# servodriver.net
KiCad netlist of a schematic drawn in EAGLE
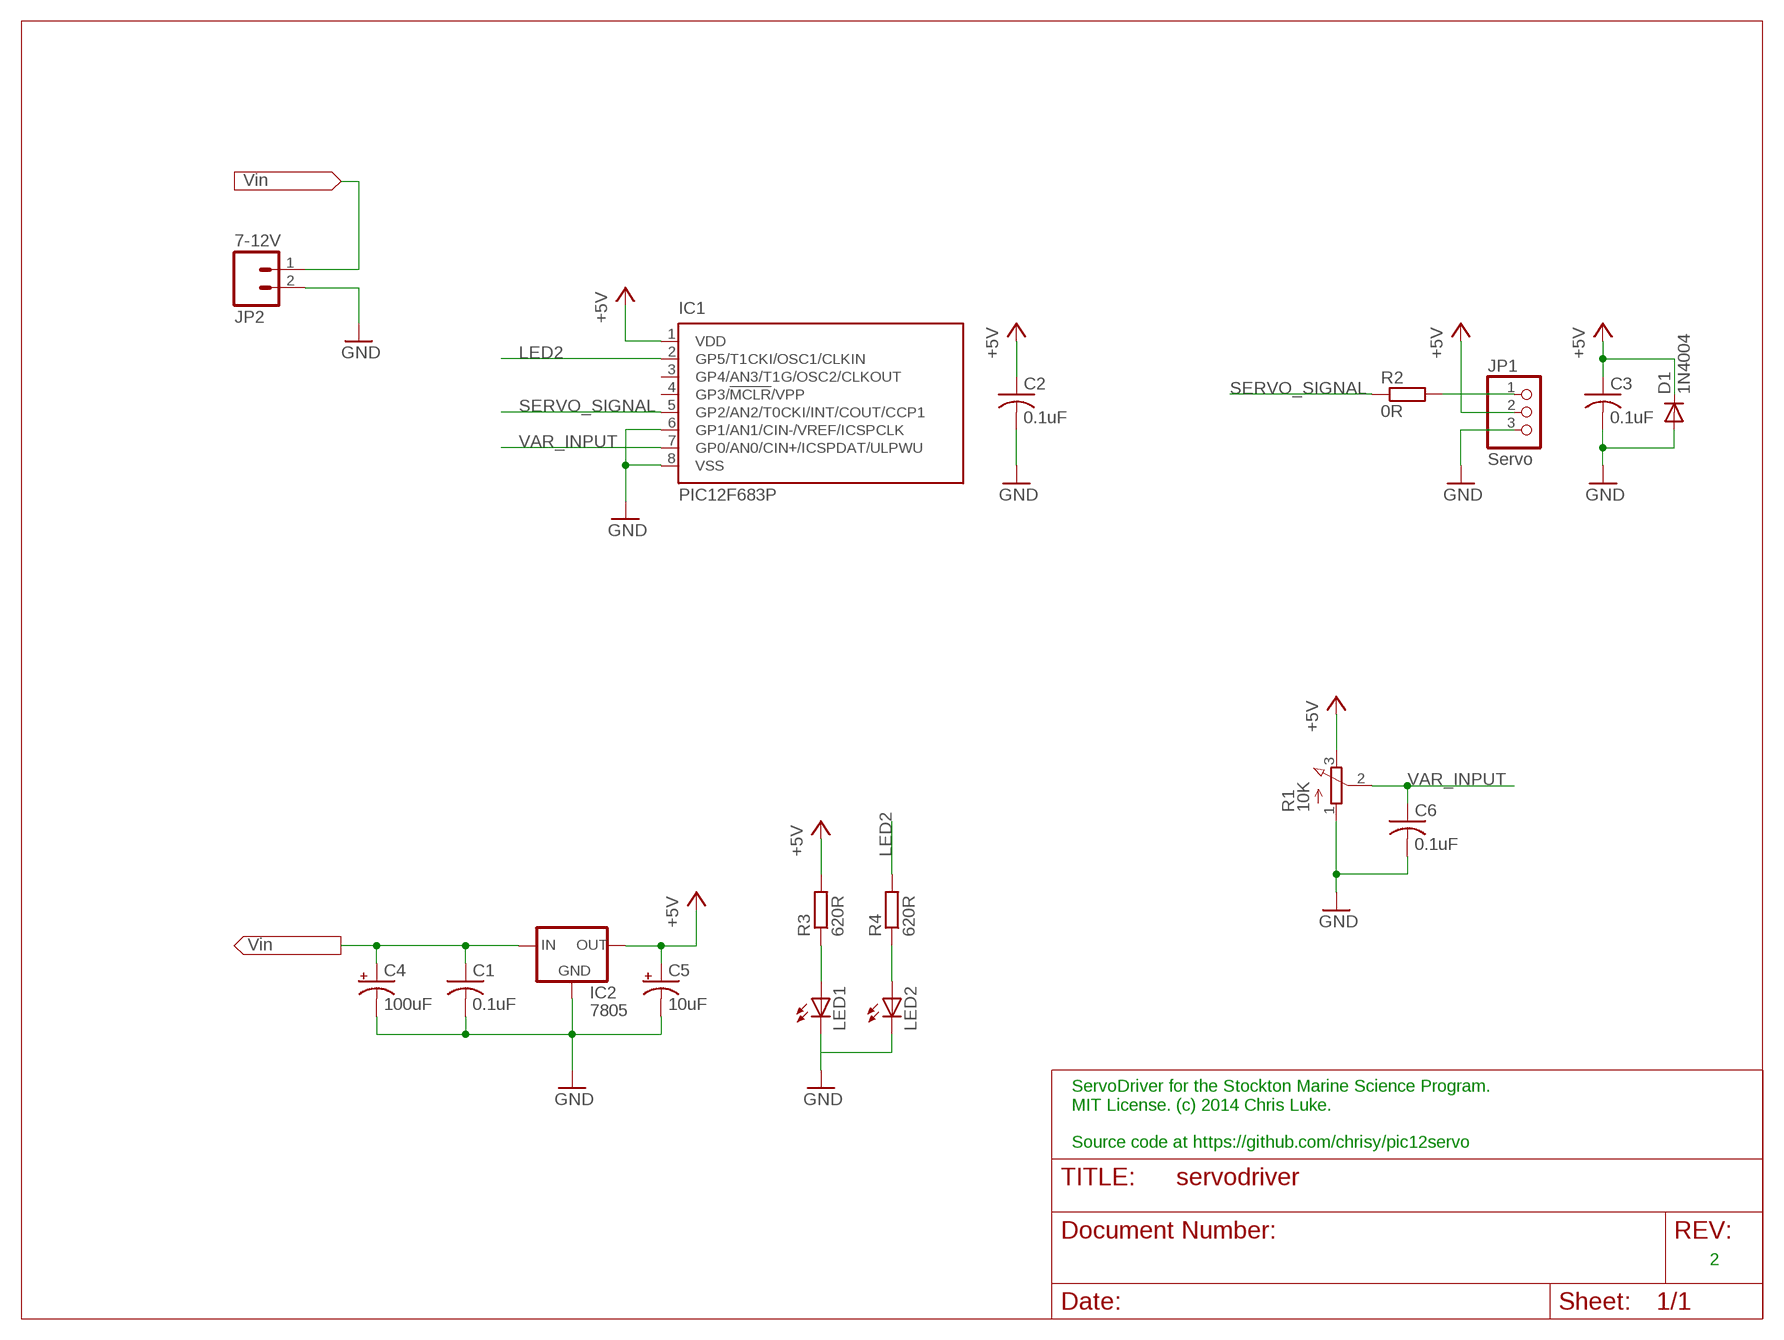
[diagram p0: schematic, sheet 1]

(export (version "E")
  (design (tool "Eeschema 10.0.6"))
  (components
    (comp (ref "C1")
      (value "0.1uF")
      (footprint "eagle-import:C025-025X050")
      (libsource (lib "eagle-import") (part "C-US025-025X050"))
    )
    (comp (ref "C2")
      (value "0.1uF")
      (footprint "eagle-import:C025-025X050")
      (libsource (lib "eagle-import") (part "C-US025-025X050"))
    )
    (comp (ref "C3")
      (value "0.1uF")
      (footprint "eagle-import:C025-025X050")
      (libsource (lib "eagle-import") (part "C-US025-025X050"))
    )
    (comp (ref "C4")
      (value "100uF")
      (footprint "eagle-import:E2,5-6")
      (libsource (lib "eagle-import") (part "CPOL-USE2.5-6"))
    )
    (comp (ref "C5")
      (value "10uF")
      (footprint "eagle-import:E2,5-6")
      (libsource (lib "eagle-import") (part "CPOL-USE2.5-6"))
    )
    (comp (ref "C6")
      (value "0.1uF")
      (footprint "eagle-import:C025-025X050")
      (libsource (lib "eagle-import") (part "C-US025-025X050"))
    )
    (comp (ref "D1")
      (value "1N4004")
      (footprint "eagle-import:DO41-10")
      (libsource (lib "eagle-import") (part "1N4004"))
    )
    (comp (ref "IC1")
      (value "PIC12F683P")
      (footprint "eagle-import:DIL8")
      (fields (field (name "MF") "MICROCHIP") (field (name "MPN") "PIC12F683-I/P"))
      (libsource (lib "eagle-import") (part "PIC12F683P"))
    )
    (comp (ref "IC2")
      (value "7805")
      (footprint "eagle-import:78XXL")
      (libsource (lib "eagle-import") (part "78XXL"))
    )
    (comp (ref "JP1")
      (value "Servo")
      (footprint "eagle-import:1X03")
      (libsource (lib "eagle-import") (part "PINHD-1X3"))
    )
    (comp (ref "JP2")
      (value "7-12V")
      (footprint "eagle-import:SCREWTERMINAL-3.5MM-2")
      (libsource (lib "eagle-import") (part "M023.5MM"))
    )
    (comp (ref "LED1")
      (value "LED3MM")
      (footprint "eagle-import:LED3MM")
      (libsource (lib "eagle-import") (part "LED3MM"))
    )
    (comp (ref "LED2")
      (value "LED3MM")
      (footprint "eagle-import:LED3MM")
      (libsource (lib "eagle-import") (part "LED3MM"))
    )
    (comp (ref "R1")
      (value "10K")
      (footprint "eagle-import:3RP_1610N")
      (libsource (lib "eagle-import") (part "3RP/1610N"))
    )
    (comp (ref "R2")
      (value "0R")
      (footprint "eagle-import:0207_10")
      (libsource (lib "eagle-import") (part "R-EU_0207/10"))
    )
    (comp (ref "R3")
      (value "620R")
      (footprint "eagle-import:0207_10")
      (libsource (lib "eagle-import") (part "R-EU_0207/10"))
    )
    (comp (ref "R4")
      (value "620R")
      (footprint "eagle-import:0207_10")
      (libsource (lib "eagle-import") (part "R-EU_0207/10"))
    )
  )
  (nets
    (net (code "1") (name "+5V") (class "Default")
      (node (ref "C2") (pin "1") (pinfunction "1_1") (pintype "passive"))
      (node (ref "C3") (pin "1") (pinfunction "1_1") (pintype "passive"))
      (node (ref "C5") (pin "+") (pinfunction "+_+") (pintype "passive"))
      (node (ref "D1") (pin "C") (pinfunction "C_C") (pintype "passive"))
      (node (ref "IC1") (pin "1") (pinfunction "VDD_1") (pintype "power_in"))
      (node (ref "IC2") (pin "OUT") (pinfunction "OUT_OUT") (pintype "passive"))
      (node (ref "JP1") (pin "2") (pinfunction "2_2") (pintype "passive"))
      (node (ref "R1") (pin "3") (pinfunction "E_3") (pintype "passive"))
      (node (ref "R3") (pin "2") (pinfunction "2_2") (pintype "passive"))
    )
    (net (code "2") (name "/LED2") (class "Default")
      (node (ref "IC1") (pin "2") (pinfunction "GP5/T1CKI/OSC1/CLKIN_2") (pintype "bidirectional"))
      (node (ref "R4") (pin "2") (pinfunction "2_2") (pintype "passive"))
    )
    (net (code "3") (name "/SERVO_SIGNAL") (class "Default")
      (node (ref "IC1") (pin "5") (pinfunction "GP2/AN2/T0CKI/INT/COUT/CCP1_5") (pintype "bidirectional"))
      (node (ref "R2") (pin "1") (pinfunction "1_1") (pintype "passive"))
    )
    (net (code "4") (name "/VAR_INPUT") (class "Default")
      (node (ref "C6") (pin "1") (pinfunction "1_1") (pintype "passive"))
      (node (ref "IC1") (pin "7") (pinfunction "GP0/AN0/CIN+/ICSPDAT/ULPWU_7") (pintype "bidirectional"))
      (node (ref "R1") (pin "2") (pinfunction "S_2") (pintype "passive"))
    )
    (net (code "5") (name "/VIN") (class "Default")
      (node (ref "C1") (pin "1") (pinfunction "1_1") (pintype "passive"))
      (node (ref "C4") (pin "+") (pinfunction "+_+") (pintype "passive"))
      (node (ref "IC2") (pin "IN") (pinfunction "IN_IN") (pintype "input"))
      (node (ref "JP2") (pin "1") (pinfunction "1_1") (pintype "passive"))
    )
    (net (code "6") (name "GND") (class "Default")
      (node (ref "C1") (pin "2") (pinfunction "2_2") (pintype "passive"))
      (node (ref "C2") (pin "2") (pinfunction "2_2") (pintype "passive"))
      (node (ref "C3") (pin "2") (pinfunction "2_2") (pintype "passive"))
      (node (ref "C4") (pin "-") (pinfunction "-_-") (pintype "passive"))
      (node (ref "C5") (pin "-") (pinfunction "-_-") (pintype "passive"))
      (node (ref "C6") (pin "2") (pinfunction "2_2") (pintype "passive"))
      (node (ref "D1") (pin "A") (pinfunction "A_A") (pintype "passive"))
      (node (ref "IC1") (pin "6") (pinfunction "GP1/AN1/CIN-/VREF/ICSPCLK_6") (pintype "bidirectional"))
      (node (ref "IC1") (pin "8") (pinfunction "VSS_8") (pintype "power_in"))
      (node (ref "IC2") (pin "GND") (pinfunction "GND_GND") (pintype "input"))
      (node (ref "JP1") (pin "3") (pinfunction "3_3") (pintype "passive"))
      (node (ref "JP2") (pin "2") (pinfunction "2_2") (pintype "passive"))
      (node (ref "LED1") (pin "K") (pinfunction "C_K") (pintype "passive"))
      (node (ref "LED2") (pin "K") (pinfunction "C_K") (pintype "passive"))
      (node (ref "R1") (pin "1") (pinfunction "A_1") (pintype "passive"))
    )
    (net (code "7") (name "Net-(JP1-Pad1)") (class "Default")
      (node (ref "JP1") (pin "1") (pinfunction "1_1") (pintype "passive"))
      (node (ref "R2") (pin "2") (pinfunction "2_2") (pintype "passive"))
    )
    (net (code "8") (name "Net-(LED1-PadA)") (class "Default")
      (node (ref "LED1") (pin "A") (pinfunction "A_A") (pintype "passive"))
      (node (ref "R3") (pin "1") (pinfunction "1_1") (pintype "passive"))
    )
    (net (code "9") (name "Net-(LED2-PadA)") (class "Default")
      (node (ref "LED2") (pin "A") (pinfunction "A_A") (pintype "passive"))
      (node (ref "R4") (pin "1") (pinfunction "1_1") (pintype "passive"))
    )
    (net (code "10") (name "unconnected-(IC1-GP3{slash}~{MCLR}{slash}VPP-Pad4)") (class "Default")
      (node (ref "IC1") (pin "4") (pinfunction "GP3/~{MCLR}/VPP_4") (pintype "bidirectional"))
    )
    (net (code "11") (name "unconnected-(IC1-GP4{slash}AN3{slash}T1G{slash}OSC2{slash}CLKOUT-Pad3)") (class "Default")
      (node (ref "IC1") (pin "3") (pinfunction "GP4/AN3/T1G/OSC2/CLKOUT_3") (pintype "bidirectional"))
    )
  )
)
